# Power.net
KiCad netlist of a schematic drawn in Altium Designer
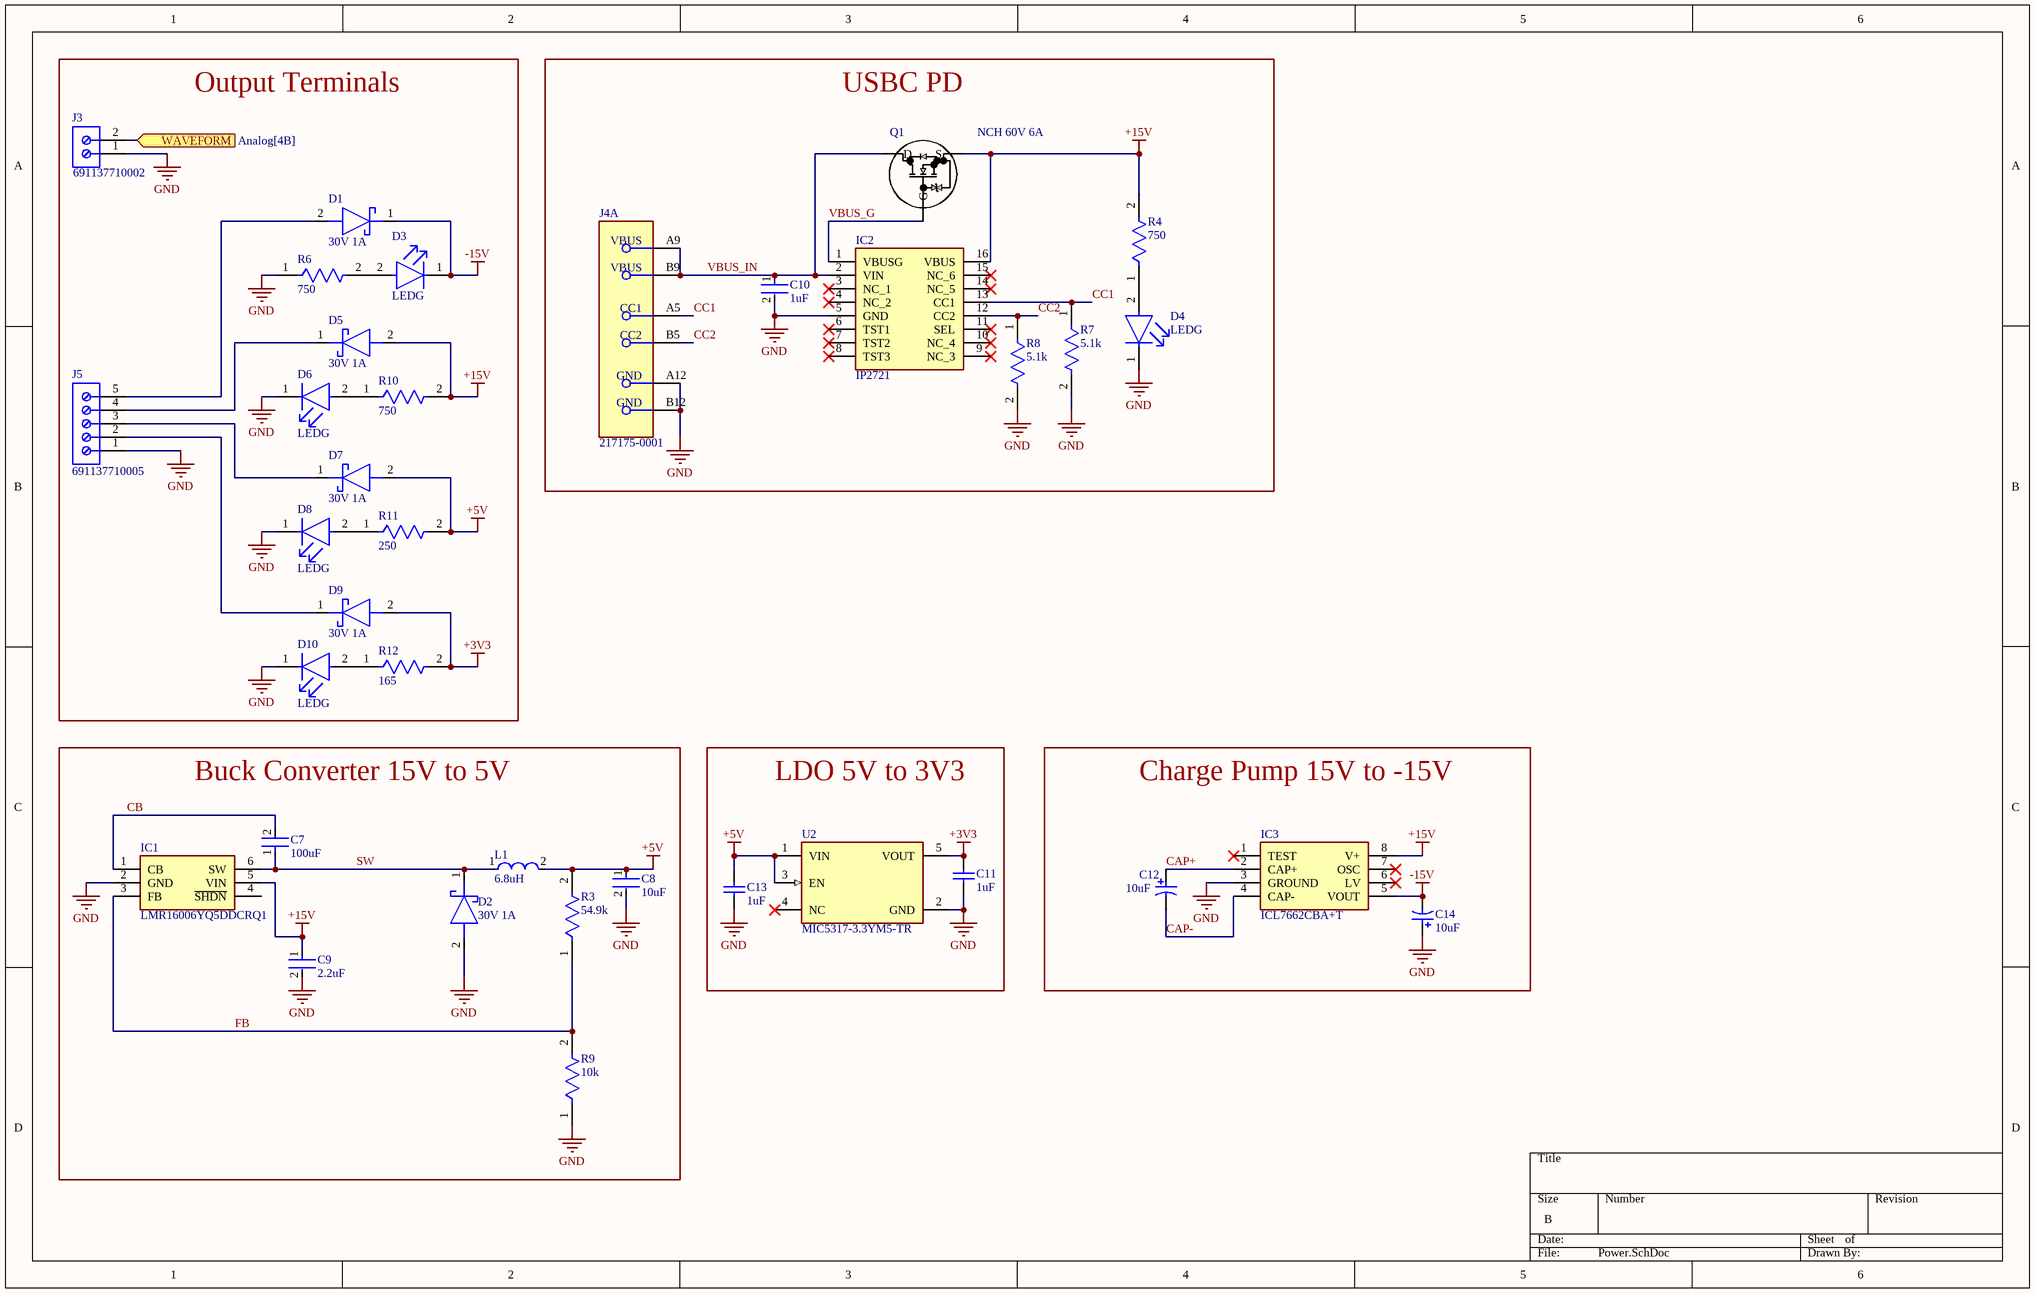
[diagram p0: Power.SchDoc]

(export (version "E")
  (design (tool "Eeschema 10.0.6"))
  (components
    (comp (ref "C7")
      (value "100uF")
      (footprint "FP-C1206C-EB-MFG")
      (description "C1206 0.10 μF C0G 10.00% 25 V X7R")
      (fields
        (field (name "TOLERANCE") "0.1")
        (field (name "OCTOPART") "https://octopart.com/c1206c104k3gactu-kemet-12901041")
      )
      (libsource (lib "Altium Content Vault") (part "b4654b650e69147ec39a6b967a45e02"))
    )
    (comp (ref "C8")
      (value "10uF")
      (footprint "FP-CL21-IPC_A")
      (description "CL21 Series 0805 10uF 25V ±10% Tolerance X5R Multilayer Ceramic Chip Capacitor")
      (fields (field (name "TOLERANCE") "10%"))
      (libsource (lib "Altium Content Vault") (part "b4654b650e69147ec39a6b967a45e02"))
    )
    (comp (ref "C9")
      (value "2.2uF")
      (footprint "FP-C0402-BB-MFG")
      (description "C0402 2,200 pF C0G 0.02 25 V")
      (fields
        (field (name "MANUFACTURER PART NUMBER") "C0402C222G3GACTU")
        (field (name "OCTOPART") "https://octopart.com/c0402c222g3gactu-kemet-87368565")
      )
      (libsource (lib "Altium Content Vault") (part "b4654b650e69147ec39a6b967a45e02"))
    )
    (comp (ref "C10")
      (value "1uF")
      (footprint "FP-CGA5L-0_3-0_1-IPC_B")
      (description "Cap Ceramic 1uF 25V X7R 20% Pad SMD 1206 +125°C Automotive T/R")
      (fields (field (name "TOLERANCE") "20%"))
      (libsource (lib "Altium Content Vault") (part "b4654b650e69147ec39a6b967a45e02"))
    )
    (comp (ref "C11")
      (value "1uF")
      (footprint "CAPC1206(3216)130_N")
      (description "CAP 1uF 10V ±5% 1206 (3216 Metric) Thickness 1.3mm SMD")
      (fields (field (name "TOLERANCE") "Â±5%"))
      (libsource (lib "Altium Content Vault") (part "CAP"))
    )
    (comp (ref "C12")
      (value "10uF")
      (footprint "VISH-293D-E_L")
      (fields (field (name "MANUFACTURER") "Vishay") (field (name "VOLTAGE") "50VDC"))
      (libsource (lib "Altium Content Vault") (part "CAP-P-2"))
    )
    (comp (ref "C13")
      (value "1uF")
      (footprint "CAPC1206(3216)130_N")
      (description "CAP 1uF 10V ±5% 1206 (3216 Metric) Thickness 1.3mm SMD")
      (fields (field (name "TOLERANCE") "Â±5%"))
      (libsource (lib "Altium Content Vault") (part "CAP"))
    )
    (comp (ref "C14")
      (value "10uF")
      (footprint "VISH-293D-E_L")
      (fields (field (name "MANUFACTURER") "Vishay") (field (name "VOLTAGE") "50VDC"))
      (libsource (lib "Altium Content Vault") (part "CAP-P-2"))
    )
    (comp (ref "D1")
      (value "30V 1A")
      (footprint "SamacSys:1SS357TPH3F")
      (description "Schottky Diode")
      (fields
        (field (name "MANUFACTURER_PART_NUMBER") "CUS10S30,H3F")
        (field (name "MOUSER PART NUMBER") "757-CUS10S30H3F")
      )
      (libsource (lib "*") (part "CUS10S30,H3F"))
    )
    (comp (ref "D2")
      (value "30V 1A")
      (footprint "SamacSys:1SS357TPH3F")
      (description "Schottky Diode")
      (fields
        (field (name "MANUFACTURER_PART_NUMBER") "CUS10S30,H3F")
        (field (name "MOUSER PART NUMBER") "757-CUS10S30H3F")
      )
      (libsource (lib "*") (part "CUS10S30,H3F"))
    )
    (comp (ref "D3")
      (value "LEDG")
      (footprint "FP-LTST-C170GKT-MFG")
      (description "LED GREEN CLEAR SMD")
      (fields (field (name "VOLTAGE") "5V"))
      (libsource (lib "Altium Content Vault") (part "8706943c75ba83719d021d2fdc84c58"))
    )
    (comp (ref "D4")
      (value "LEDG")
      (footprint "FP-LTST-C170GKT-MFG")
      (description "LED GREEN CLEAR SMD")
      (fields (field (name "VOLTAGE") "5V"))
      (libsource (lib "Altium Content Vault") (part "8706943c75ba83719d021d2fdc84c58"))
    )
    (comp (ref "D5")
      (value "30V 1A")
      (footprint "SamacSys:1SS357TPH3F")
      (description "Schottky Diode")
      (fields
        (field (name "MANUFACTURER_PART_NUMBER") "CUS10S30,H3F")
        (field (name "MOUSER PART NUMBER") "757-CUS10S30H3F")
      )
      (libsource (lib "*") (part "CUS10S30,H3F"))
    )
    (comp (ref "D6")
      (value "LEDG")
      (footprint "FP-LTST-C170GKT-MFG")
      (description "LED GREEN CLEAR SMD")
      (fields (field (name "VOLTAGE") "5V"))
      (libsource (lib "Altium Content Vault") (part "8706943c75ba83719d021d2fdc84c58"))
    )
    (comp (ref "D7")
      (value "30V 1A")
      (footprint "SamacSys:1SS357TPH3F")
      (description "Schottky Diode")
      (fields
        (field (name "MANUFACTURER_PART_NUMBER") "CUS10S30,H3F")
        (field (name "MOUSER PART NUMBER") "757-CUS10S30H3F")
      )
      (libsource (lib "*") (part "CUS10S30,H3F"))
    )
    (comp (ref "D8")
      (value "LEDG")
      (footprint "FP-LTST-C170GKT-MFG")
      (description "LED GREEN CLEAR SMD")
      (fields (field (name "VOLTAGE") "5V"))
      (libsource (lib "Altium Content Vault") (part "8706943c75ba83719d021d2fdc84c58"))
    )
    (comp (ref "D9")
      (value "30V 1A")
      (footprint "SamacSys:1SS357TPH3F")
      (description "Schottky Diode")
      (fields
        (field (name "MANUFACTURER_PART_NUMBER") "CUS10S30,H3F")
        (field (name "MOUSER PART NUMBER") "757-CUS10S30H3F")
      )
      (libsource (lib "*") (part "CUS10S30,H3F"))
    )
    (comp (ref "D10")
      (value "LEDG")
      (footprint "FP-LTST-C170GKT-MFG")
      (description "LED GREEN CLEAR SMD")
      (fields (field (name "VOLTAGE") "5V"))
      (libsource (lib "Altium Content Vault") (part "8706943c75ba83719d021d2fdc84c58"))
    )
    (comp (ref "IC1")
      (value "LMR16006YQ5DDCRQ1")
      (footprint "SamacSys:SOT95P280X110-6N")
      (description "Integrated Circuit")
      (fields (field (name "MOUSER PART NUMBER") "595-MR16006YQ5DDCRQ1"))
      (libsource (lib "*") (part "LMR16006YQ5DDCRQ1"))
    )
    (comp (ref "IC2")
      (value "IP2721")
      (footprint "SamacSys:SOP65P640X120-16N")
      (description "Integrated Circuit")
      (libsource (lib "*") (part "IP2721"))
    )
    (comp (ref "IC3")
      (value "ICL7662CBA+T")
      (footprint "SamacSys:SOIC127P600X175-8N")
      (description "Integrated Circuit")
      (fields (field (name "MOUSER PART NUMBER") "700-ICL7662CBAT"))
      (libsource (lib "*") (part "ICL7662CBA+T"))
    )
    (comp (ref "J3")
      (value "691137710002")
      (footprint "691137710002")
      (libsource (lib "Altium Content Vault") (part "TBL - 1R - 02P - Screw"))
    )
    (comp (ref "J4")
      (value "217175-0001")
      (footprint "FP-217175-0001-MFG")
      (description "CONN RCP USB2.0 C 6+18P SMD RA")
      (libsource (lib "Altium Content Vault") (part "6a66c69350f09309f94811689c98437"))
    )
    (comp (ref "J5")
      (value "691137710005")
      (footprint "691137710005")
      (libsource (lib "Altium Content Vault") (part "TBL - 1R - 05P - Screw"))
    )
    (comp (ref "L1")
      (value "6.8uH")
      (footprint "FP-LQH3NPH_ME-MFG")
      (description "Wire Wound Ferrite Inductor for Power Lines For Automotive 6.8μH ±20% 0.168Ω 1450mA 1212")
      (libsource (lib "Altium Content Vault") (part "725321dda6339637d4d059423bc1c3c"))
    )
    (comp (ref "Q1")
      (value "NCH 60V 6A")
      (footprint "SOT-323F_2-2U1S_UFM_TOS")
      (description "N-ch MOSFET, 60 V, 6.0 A, 0.036 Î©@10V, SOT-323F(UFM)")
      (fields
        (field (name "MANUFACTURER_PART_NUMBER") "SSM3K341TU,LF")
        (field (name "COPYRIGHT") "Copyright (C) 2025 Ultra Librarian. All rights reserved.")
      )
      (libsource (lib "Connectors") (part "SSM3K341TU,LF"))
    )
    (comp (ref "R3")
      (value "54.9k")
      (footprint "FP-TFCR0603-IPC_C")
      (description "RES Thin Film,  54.9kΩ, 0.25%, 0.1W, 50ppm/°C, 0603")
      (libsource (lib "Altium Content Vault") (part "1029c3af85768c4190bb7ad29bc67b5"))
    )
    (comp (ref "R4")
      (value "750")
      (footprint "FP-AT0805-IPC_C")
      (description "Thin Film Chip Resistors Automotive Grade 10kΩ 0.1% 50ppm/°C 0805")
      (libsource (lib "Altium Content Vault") (part "1029c3af85768c4190bb7ad29bc67b5"))
    )
    (comp (ref "R6")
      (value "750")
      (footprint "FP-RMCF0805-MFG")
      (description "6.8kΩ ±5% 0.125W 0805 Thick Film Chip Resistor AEC-Q200 compliant")
      (fields (field (name "TOLERANCE") "5%"))
      (libsource (lib "Altium Content Vault") (part "1029c3af85768c4190bb7ad29bc67b5"))
    )
    (comp (ref "R7")
      (value "5.1k")
      (footprint "FP-TFCR0603-IPC_A")
      (description "RES Thin Film,  5.1kΩ, 0.25%, 0.1W, 25ppm/°C, 0603")
      (libsource (lib "Altium Content Vault") (part "1029c3af85768c4190bb7ad29bc67b5"))
    )
    (comp (ref "R8")
      (value "5.1k")
      (footprint "FP-TFCR0603-IPC_A")
      (description "RES Thin Film,  5.1kΩ, 0.25%, 0.1W, 25ppm/°C, 0603")
      (libsource (lib "Altium Content Vault") (part "1029c3af85768c4190bb7ad29bc67b5"))
    )
    (comp (ref "R9")
      (value "10k")
      (footprint "FP-AT0805-IPC_C")
      (description "Thin Film Chip Resistors Automotive Grade 10kΩ 0.1% 50ppm/°C 0805")
      (libsource (lib "Altium Content Vault") (part "1029c3af85768c4190bb7ad29bc67b5"))
    )
    (comp (ref "R10")
      (value "750")
      (footprint "FP-RMCF0805-MFG")
      (description "6.8kΩ ±5% 0.125W 0805 Thick Film Chip Resistor AEC-Q200 compliant")
      (fields (field (name "TOLERANCE") "5%"))
      (libsource (lib "Altium Content Vault") (part "1029c3af85768c4190bb7ad29bc67b5"))
    )
    (comp (ref "R11")
      (value "250")
      (footprint "FP-RMCF0805-MFG")
      (description "0805 250 Ohms 0.25W")
      (fields (field (name "TOLERANCE") "5%"))
      (libsource (lib "Altium Content Vault") (part "1029c3af85768c4190bb7ad29bc67b5"))
    )
    (comp (ref "R12")
      (value "165")
      (footprint "FP-TFCR0603-IPC_B")
      (description "RES Thin Film,  620Ω, 0.25%, 0.1W, 25ppm/°C, 0603")
      (libsource (lib "Altium Content Vault") (part "1029c3af85768c4190bb7ad29bc67b5"))
    )
    (comp (ref "U2")
      (value "MIC5317-3.3YM5-TR")
      (footprint "FP-SOT23-5LD-PL-1-MFG")
      (description "IC REG LINEAR 3.3V 150MA SOT23-5")
      (libsource (lib "Altium Content Vault") (part "0a093dae7315cdc977fd108dde87457"))
    )
  )
  (nets
    (net (code "1") (name "+3V3") (class "Default")
      (node (ref "C11") (pin "2") (pinfunction "2_2") (pintype "passive"))
      (node (ref "D9") (pin "2") (pinfunction "A_2") (pintype "passive"))
      (node (ref "R12") (pin "2") (pinfunction "2_2") (pintype "passive"))
      (node (ref "U2") (pin "5") (pinfunction "VOUT_5") (pintype "power_in"))
    )
    (net (code "2") (name "+5V") (class "Default")
      (node (ref "C13") (pin "2") (pinfunction "2_2") (pintype "passive"))
      (node (ref "C8") (pin "1") (pinfunction "1_1") (pintype "passive"))
      (node (ref "D7") (pin "2") (pinfunction "A_2") (pintype "passive"))
      (node (ref "L1") (pin "2") (pinfunction "2_2") (pintype "passive"))
      (node (ref "R11") (pin "2") (pinfunction "2_2") (pintype "passive"))
      (node (ref "R3") (pin "2") (pinfunction "2_2") (pintype "passive"))
      (node (ref "U2") (pin "1") (pinfunction "VIN_1") (pintype "power_in"))
      (node (ref "U2") (pin "3") (pinfunction "EN_3") (pintype "input"))
    )
    (net (code "3") (name "+15V") (class "Default")
      (node (ref "C9") (pin "1") (pinfunction "1_1") (pintype "passive"))
      (node (ref "D5") (pin "2") (pinfunction "A_2") (pintype "passive"))
      (node (ref "IC1") (pin "5") (pinfunction "VIN_5") (pintype "passive"))
      (node (ref "IC2") (pin "16") (pinfunction "VBUS_16") (pintype "passive"))
      (node (ref "IC3") (pin "8") (pinfunction "V+_8") (pintype "passive"))
      (node (ref "Q1") (pin "2") (pinfunction "S_2") (pintype "passive"))
      (node (ref "R10") (pin "2") (pinfunction "2_2") (pintype "passive"))
      (node (ref "R4") (pin "2") (pinfunction "2_2") (pintype "passive"))
    )
    (net (code "4") (name "-15V") (class "Default")
      (node (ref "C14") (pin "2") (pinfunction "2_2") (pintype "passive"))
      (node (ref "D1") (pin "1") (pinfunction "K_1") (pintype "passive"))
      (node (ref "D3") (pin "1") (pinfunction "C_1") (pintype "passive"))
      (node (ref "IC3") (pin "5") (pinfunction "VOUT_5") (pintype "passive"))
    )
    (net (code "5") (name "/CAP+") (class "Default")
      (node (ref "C12") (pin "1") (pinfunction "1_1") (pintype "passive"))
      (node (ref "IC3") (pin "2") (pinfunction "CAP+_2") (pintype "passive"))
    )
    (net (code "6") (name "/CAP-") (class "Default")
      (node (ref "C12") (pin "2") (pinfunction "2_2") (pintype "passive"))
      (node (ref "IC3") (pin "4") (pinfunction "CAP-_4") (pintype "passive"))
    )
    (net (code "7") (name "/CB") (class "Default")
      (node (ref "C7") (pin "2") (pinfunction "2_2") (pintype "passive"))
      (node (ref "IC1") (pin "1") (pinfunction "CB_1") (pintype "passive"))
    )
    (net (code "8") (name "/CC1") (class "Default")
      (node (ref "IC2") (pin "13") (pinfunction "CC1_13") (pintype "passive"))
      (node (ref "J4") (pin "A5") (pinfunction "CC1_A5") (pintype "passive"))
      (node (ref "R7") (pin "1") (pinfunction "1_1") (pintype "passive"))
    )
    (net (code "9") (name "/CC2") (class "Default")
      (node (ref "IC2") (pin "12") (pinfunction "CC2_12") (pintype "passive"))
      (node (ref "J4") (pin "B5") (pinfunction "CC2_B5") (pintype "passive"))
      (node (ref "R8") (pin "1") (pinfunction "1_1") (pintype "passive"))
    )
    (net (code "10") (name "/FB") (class "Default")
      (node (ref "IC1") (pin "3") (pinfunction "FB_3") (pintype "passive"))
      (node (ref "R3") (pin "1") (pinfunction "1_1") (pintype "passive"))
      (node (ref "R9") (pin "2") (pinfunction "2_2") (pintype "passive"))
    )
    (net (code "11") (name "/SW") (class "Default")
      (node (ref "C7") (pin "1") (pinfunction "1_1") (pintype "passive"))
      (node (ref "D2") (pin "1") (pinfunction "K_1") (pintype "passive"))
      (node (ref "IC1") (pin "6") (pinfunction "SW_6") (pintype "passive"))
      (node (ref "L1") (pin "1") (pinfunction "1_1") (pintype "passive"))
    )
    (net (code "12") (name "/VBUS_G") (class "Default")
      (node (ref "IC2") (pin "1") (pinfunction "VBUSG_1") (pintype "passive"))
      (node (ref "Q1") (pin "1") (pinfunction "G_1") (pintype "passive"))
    )
    (net (code "13") (name "/VBUS_IN") (class "Default")
      (node (ref "C10") (pin "1") (pinfunction "1_1") (pintype "passive"))
      (node (ref "IC2") (pin "2") (pinfunction "VIN_2") (pintype "passive"))
      (node (ref "J4") (pin "A9") (pinfunction "VBUS_A9") (pintype "power_in"))
      (node (ref "J4") (pin "B9") (pinfunction "VBUS_B9") (pintype "power_in"))
      (node (ref "Q1") (pin "3") (pinfunction "D_3") (pintype "passive"))
    )
    (net (code "14") (name "/WAVEFORM") (class "Default")
      (node (ref "J3") (pin "2") (pinfunction "2_2") (pintype "passive"))
    )
    (net (code "15") (name "GND") (class "Default")
      (node (ref "C10") (pin "2") (pinfunction "2_2") (pintype "passive"))
      (node (ref "C11") (pin "1") (pinfunction "1_1") (pintype "passive"))
      (node (ref "C13") (pin "1") (pinfunction "1_1") (pintype "passive"))
      (node (ref "C14") (pin "1") (pinfunction "1_1") (pintype "passive"))
      (node (ref "C8") (pin "2") (pinfunction "2_2") (pintype "passive"))
      (node (ref "C9") (pin "2") (pinfunction "2_2") (pintype "passive"))
      (node (ref "D10") (pin "1") (pinfunction "C_1") (pintype "passive"))
      (node (ref "D2") (pin "2") (pinfunction "A_2") (pintype "passive"))
      (node (ref "D4") (pin "1") (pinfunction "C_1") (pintype "passive"))
      (node (ref "D6") (pin "1") (pinfunction "C_1") (pintype "passive"))
      (node (ref "D8") (pin "1") (pinfunction "C_1") (pintype "passive"))
      (node (ref "IC1") (pin "2") (pinfunction "GND_2") (pintype "passive"))
      (node (ref "IC2") (pin "5") (pinfunction "GND_5") (pintype "passive"))
      (node (ref "IC3") (pin "3") (pinfunction "GROUND_3") (pintype "passive"))
      (node (ref "J3") (pin "1") (pinfunction "1_1") (pintype "passive"))
      (node (ref "J4") (pin "A12") (pinfunction "GND_A12") (pintype "power_in"))
      (node (ref "J4") (pin "B12") (pinfunction "GND_B12") (pintype "power_in"))
      (node (ref "J5") (pin "1") (pinfunction "1_1") (pintype "passive"))
      (node (ref "R6") (pin "1") (pinfunction "1_1") (pintype "passive"))
      (node (ref "R7") (pin "2") (pinfunction "2_2") (pintype "passive"))
      (node (ref "R8") (pin "2") (pinfunction "2_2") (pintype "passive"))
      (node (ref "R9") (pin "1") (pinfunction "1_1") (pintype "passive"))
      (node (ref "U2") (pin "2") (pinfunction "GND_2") (pintype "power_in"))
    )
    (net (code "16") (name "Net-(D1-A)") (class "Default")
      (node (ref "D1") (pin "2") (pinfunction "A_2") (pintype "passive"))
      (node (ref "J5") (pin "5") (pinfunction "5_5") (pintype "passive"))
    )
    (net (code "17") (name "Net-(D3-A)") (class "Default")
      (node (ref "D3") (pin "2") (pinfunction "A_2") (pintype "passive"))
      (node (ref "R6") (pin "2") (pinfunction "2_2") (pintype "passive"))
    )
    (net (code "18") (name "Net-(D4-A)") (class "Default")
      (node (ref "D4") (pin "2") (pinfunction "A_2") (pintype "passive"))
      (node (ref "R4") (pin "1") (pinfunction "1_1") (pintype "passive"))
    )
    (net (code "19") (name "Net-(D5-K)") (class "Default")
      (node (ref "D5") (pin "1") (pinfunction "K_1") (pintype "passive"))
      (node (ref "J5") (pin "4") (pinfunction "4_4") (pintype "passive"))
    )
    (net (code "20") (name "Net-(D6-A)") (class "Default")
      (node (ref "D6") (pin "2") (pinfunction "A_2") (pintype "passive"))
      (node (ref "R10") (pin "1") (pinfunction "1_1") (pintype "passive"))
    )
    (net (code "21") (name "Net-(D7-K)") (class "Default")
      (node (ref "D7") (pin "1") (pinfunction "K_1") (pintype "passive"))
      (node (ref "J5") (pin "3") (pinfunction "3_3") (pintype "passive"))
    )
    (net (code "22") (name "Net-(D8-A)") (class "Default")
      (node (ref "D8") (pin "2") (pinfunction "A_2") (pintype "passive"))
      (node (ref "R11") (pin "1") (pinfunction "1_1") (pintype "passive"))
    )
    (net (code "23") (name "Net-(D9-K)") (class "Default")
      (node (ref "D9") (pin "1") (pinfunction "K_1") (pintype "passive"))
      (node (ref "J5") (pin "2") (pinfunction "2_2") (pintype "passive"))
    )
    (net (code "24") (name "Net-(D10-A)") (class "Default")
      (node (ref "D10") (pin "2") (pinfunction "A_2") (pintype "passive"))
      (node (ref "R12") (pin "1") (pinfunction "1_1") (pintype "passive"))
    )
    (net (code "25") (name "unconnected-(IC1-~{SHDN}-Pad4)") (class "Default")
      (node (ref "IC1") (pin "4") (pinfunction "~{SHDN}_4") (pintype "passive"))
    )
    (net (code "26") (name "unconnected-(IC2-NC_1-Pad3)") (class "Default")
      (node (ref "IC2") (pin "3") (pinfunction "NC_1_3") (pintype "passive+no_connect"))
    )
    (net (code "27") (name "unconnected-(IC2-NC_2-Pad4)") (class "Default")
      (node (ref "IC2") (pin "4") (pinfunction "NC_2_4") (pintype "passive+no_connect"))
    )
    (net (code "28") (name "unconnected-(IC2-NC_3-Pad9)") (class "Default")
      (node (ref "IC2") (pin "9") (pinfunction "NC_3_9") (pintype "passive+no_connect"))
    )
    (net (code "29") (name "unconnected-(IC2-NC_4-Pad10)") (class "Default")
      (node (ref "IC2") (pin "10") (pinfunction "NC_4_10") (pintype "passive+no_connect"))
    )
    (net (code "30") (name "unconnected-(IC2-NC_5-Pad14)") (class "Default")
      (node (ref "IC2") (pin "14") (pinfunction "NC_5_14") (pintype "passive+no_connect"))
    )
    (net (code "31") (name "unconnected-(IC2-NC_6-Pad15)") (class "Default")
      (node (ref "IC2") (pin "15") (pinfunction "NC_6_15") (pintype "passive+no_connect"))
    )
    (net (code "32") (name "unconnected-(IC2-SEL-Pad11)") (class "Default")
      (node (ref "IC2") (pin "11") (pinfunction "SEL_11") (pintype "passive+no_connect"))
    )
    (net (code "33") (name "unconnected-(IC2-TST1-Pad6)") (class "Default")
      (node (ref "IC2") (pin "6") (pinfunction "TST1_6") (pintype "passive+no_connect"))
    )
    (net (code "34") (name "unconnected-(IC2-TST2-Pad7)") (class "Default")
      (node (ref "IC2") (pin "7") (pinfunction "TST2_7") (pintype "passive+no_connect"))
    )
    (net (code "35") (name "unconnected-(IC2-TST3-Pad8)") (class "Default")
      (node (ref "IC2") (pin "8") (pinfunction "TST3_8") (pintype "passive+no_connect"))
    )
    (net (code "36") (name "unconnected-(IC3-LV-Pad6)") (class "Default")
      (node (ref "IC3") (pin "6") (pinfunction "LV_6") (pintype "passive+no_connect"))
    )
    (net (code "37") (name "unconnected-(IC3-OSC-Pad7)") (class "Default")
      (node (ref "IC3") (pin "7") (pinfunction "OSC_7") (pintype "passive+no_connect"))
    )
    (net (code "38") (name "unconnected-(IC3-TEST-Pad1)") (class "Default")
      (node (ref "IC3") (pin "1") (pinfunction "TEST_1") (pintype "passive+no_connect"))
    )
    (net (code "39") (name "unconnected-(U2-NC-Pad4)") (class "Default")
      (node (ref "U2") (pin "4") (pinfunction "NC_4") (pintype "passive+no_connect"))
    )
  )
)
